# amp-LNA-BGB741L7ESD.net
KiCad netlist of a schematic drawn in EAGLE
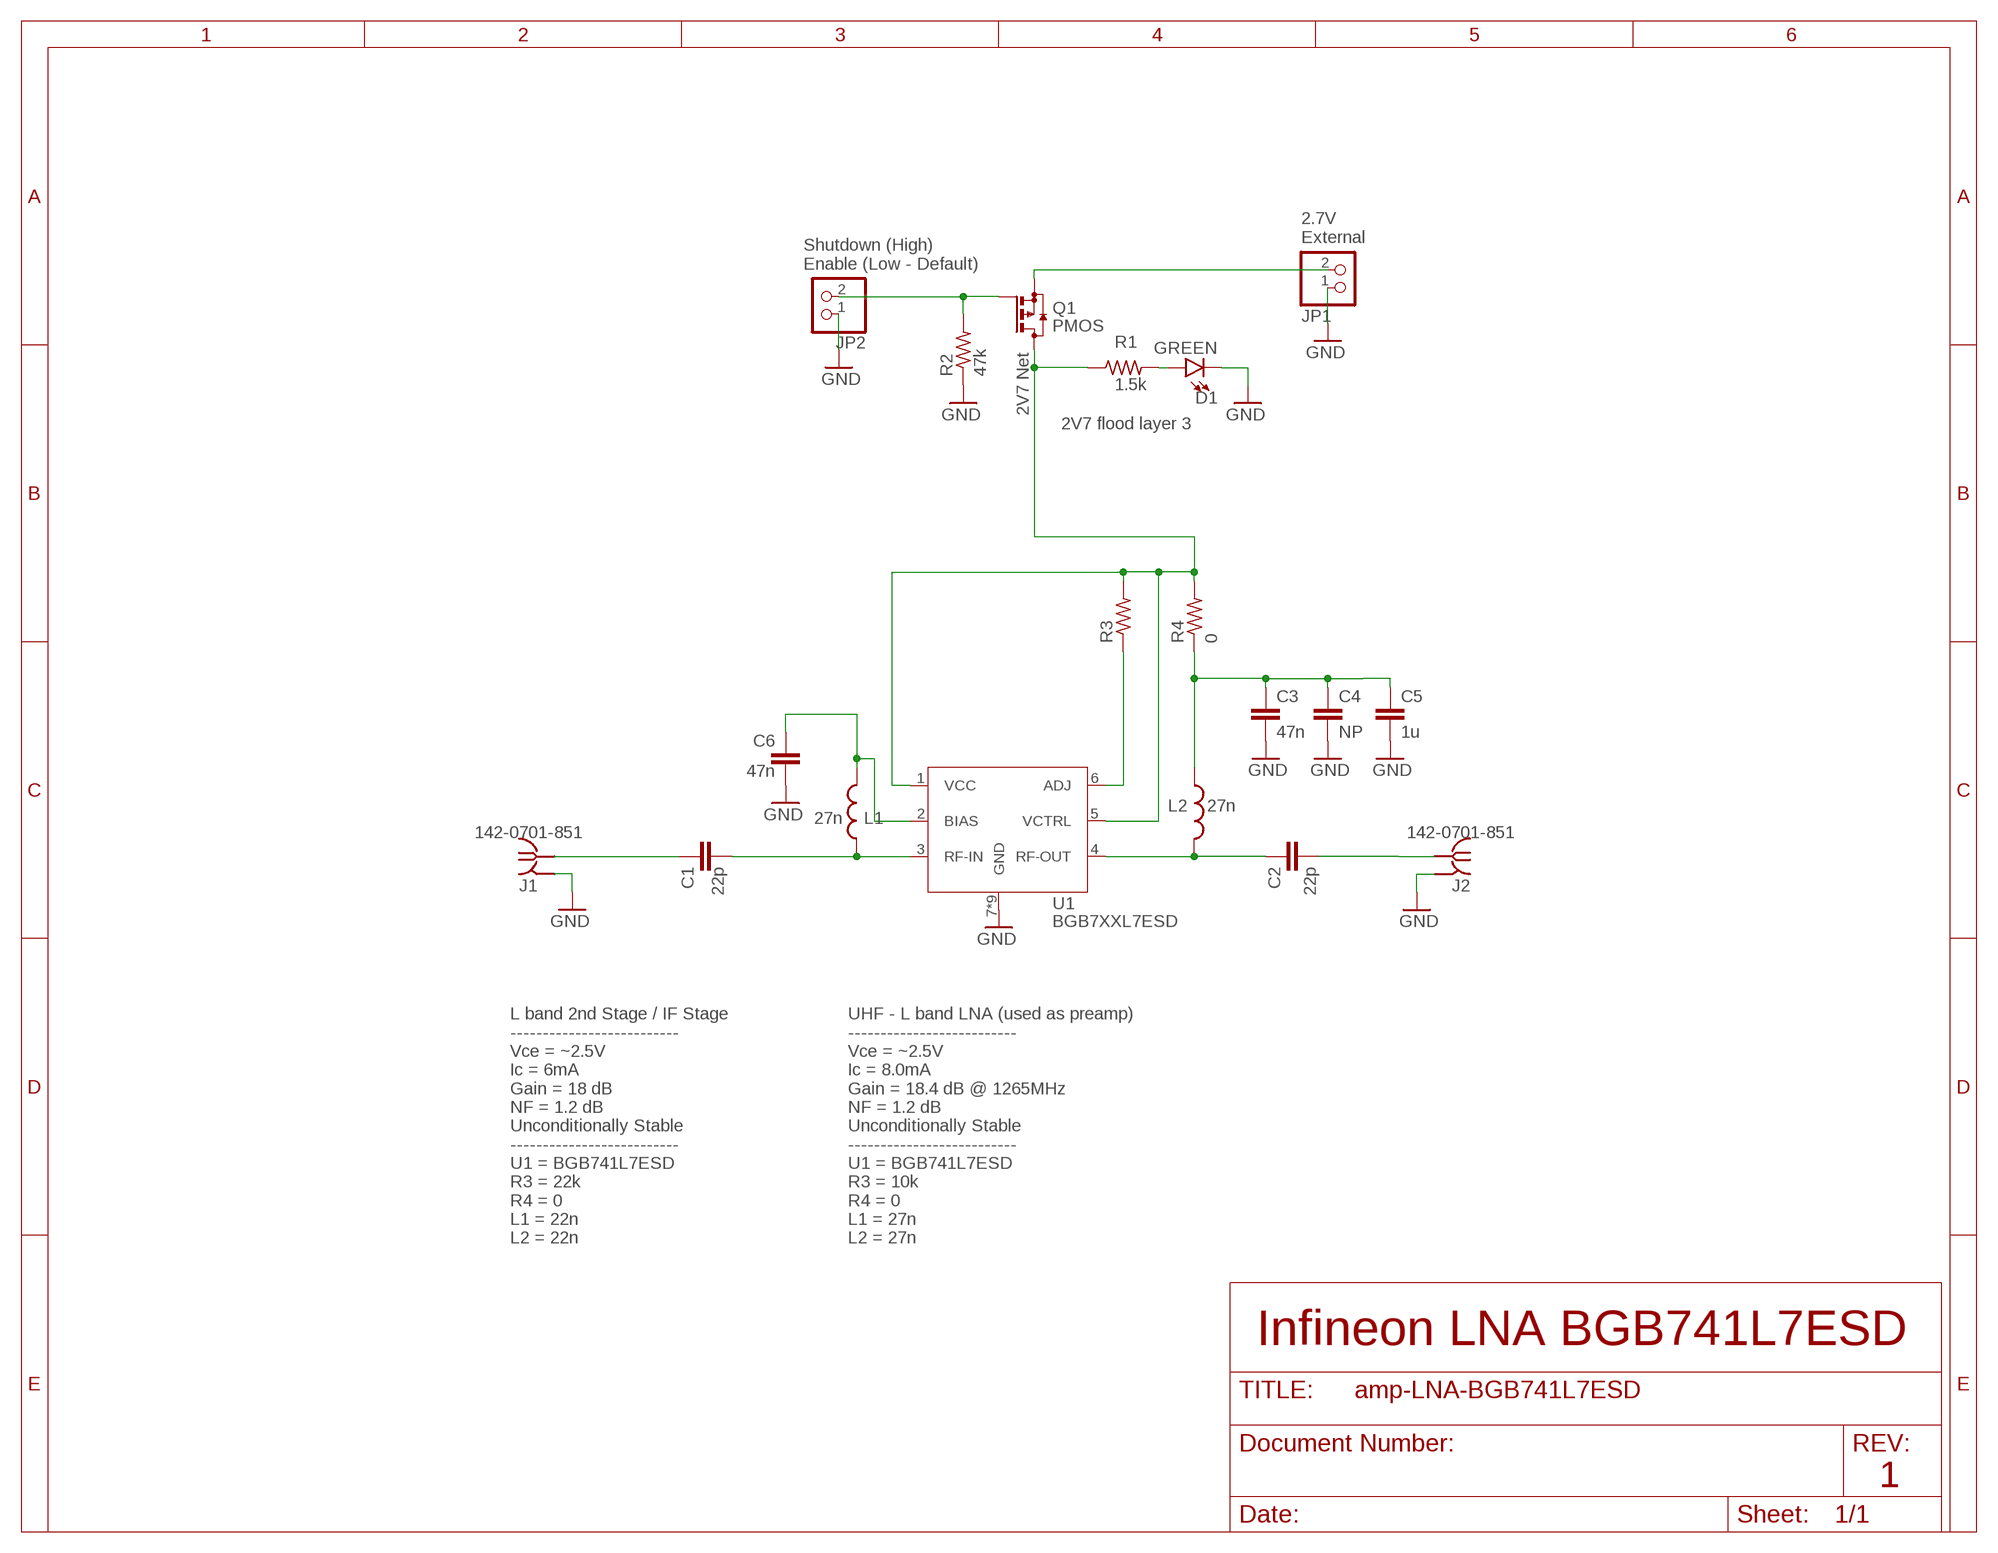
[diagram p0: schematic, sheet 1]

(export (version "E")
  (design (tool "Eeschema 10.0.6"))
  (components
    (comp (ref "C1")
      (value "22p")
      (footprint "eagle-import:.0402-C-NOSILK")
      (libsource (lib "eagle-import") (part "C-EU0402-C-NOSILK"))
    )
    (comp (ref "C2")
      (value "22p")
      (footprint "eagle-import:.0402-C-NOSILK")
      (libsource (lib "eagle-import") (part "C-EU0402-C-NOSILK"))
    )
    (comp (ref "C3")
      (value "47n")
      (footprint "eagle-import:.0603-B-NOSILK")
      (libsource (lib "eagle-import") (part "C-EU0603-B-NOSILK"))
    )
    (comp (ref "C4")
      (value "NP")
      (footprint "eagle-import:.0603-B-NOSILK")
      (libsource (lib "eagle-import") (part "C-EU0603-B-NOSILK"))
    )
    (comp (ref "C5")
      (value "1u")
      (footprint "eagle-import:.0603-B-NOSILK")
      (libsource (lib "eagle-import") (part "C-EU0603-B-NOSILK"))
    )
    (comp (ref "C6")
      (value "47n")
      (footprint "eagle-import:.0603-B-NOSILK")
      (libsource (lib "eagle-import") (part "C-EU0603-B-NOSILK"))
    )
    (comp (ref "D1")
      (value "GREEN")
      (footprint "eagle-import:LED-0603")
      (libsource (lib "eagle-import") (part "LED-GREEN0603"))
    )
    (comp (ref "J1")
      (value "142-0701-851")
      (footprint "eagle-import:142-0701-851")
      (libsource (lib "eagle-import") (part "142-0701-851"))
    )
    (comp (ref "J2")
      (value "142-0701-851")
      (footprint "eagle-import:142-0701-851")
      (libsource (lib "eagle-import") (part "142-0701-851"))
    )
    (comp (ref "JP1")
      (value "PINHD-1X2")
      (footprint "eagle-import:1X02")
      (libsource (lib "eagle-import") (part "PINHD-1X2"))
    )
    (comp (ref "JP2")
      (value "PINHD-1X2")
      (footprint "eagle-import:1X02")
      (libsource (lib "eagle-import") (part "PINHD-1X2"))
    )
    (comp (ref "L1")
      (value "27n")
      (footprint "eagle-import:.0603-C-NOSILK")
      (libsource (lib "eagle-import") (part "L-US0603-C-NOSILK"))
    )
    (comp (ref "L2")
      (value "27n")
      (footprint "eagle-import:.0603-C-NOSILK")
      (libsource (lib "eagle-import") (part "L-US0603-C-NOSILK"))
    )
    (comp (ref "Q1")
      (value "PMOS")
      (footprint "eagle-import:SOT23")
      (libsource (lib "eagle-import") (part "BSS84"))
    )
    (comp (ref "R1")
      (value "1.5k")
      (footprint "eagle-import:.0603-B-NOSILK")
      (libsource (lib "eagle-import") (part "R-US_0603-B-NOSILK"))
    )
    (comp (ref "R2")
      (value "47k")
      (footprint "eagle-import:.0402-B-NOSILK")
      (libsource (lib "eagle-import") (part "R-US_0402-B-NOSILK"))
    )
    (comp (ref "R3")
      (value "27k / NP")
      (footprint "eagle-import:.0603-B-NOSILK")
      (libsource (lib "eagle-import") (part "R-US_0603-B-NOSILK"))
    )
    (comp (ref "R4")
      (value "0")
      (footprint "eagle-import:.0603-B-NOSILK")
      (libsource (lib "eagle-import") (part "R-US_0603-B-NOSILK"))
    )
    (comp (ref "U1")
      (value "BGB7XXL7ESD")
      (footprint "eagle-import:BGB7XXL7ESD")
      (libsource (lib "eagle-import") (part "BGB7XXL7ESD"))
    )
  )
  (nets
    (net (code "1") (name "GND") (class "Default")
      (node (ref "C3") (pin "2") (pinfunction "2_2") (pintype "passive"))
      (node (ref "C4") (pin "2") (pinfunction "2_2") (pintype "passive"))
      (node (ref "C5") (pin "2") (pinfunction "2_2") (pintype "passive"))
      (node (ref "C6") (pin "2") (pinfunction "2_2") (pintype "passive"))
      (node (ref "D1") (pin "C") (pinfunction "C_C") (pintype "passive"))
      (node (ref "J1") (pin "GND1") (pinfunction "GND_GND1") (pintype "bidirectional"))
      (node (ref "J1") (pin "GND2") (pinfunction "GND_GND2") (pintype "bidirectional"))
      (node (ref "J1") (pin "GND3") (pinfunction "GND_GND3") (pintype "bidirectional"))
      (node (ref "J1") (pin "GND4") (pinfunction "GND_GND4") (pintype "bidirectional"))
      (node (ref "J2") (pin "GND1") (pinfunction "GND_GND1") (pintype "bidirectional"))
      (node (ref "J2") (pin "GND2") (pinfunction "GND_GND2") (pintype "bidirectional"))
      (node (ref "J2") (pin "GND3") (pinfunction "GND_GND3") (pintype "bidirectional"))
      (node (ref "J2") (pin "GND4") (pinfunction "GND_GND4") (pintype "bidirectional"))
      (node (ref "JP1") (pin "1") (pinfunction "1_1") (pintype "passive"))
      (node (ref "JP2") (pin "1") (pinfunction "1_1") (pintype "passive"))
      (node (ref "R2") (pin "1") (pinfunction "1_1") (pintype "passive"))
      (node (ref "U1") (pin "10") (pinfunction "GND_10") (pintype "power_in"))
      (node (ref "U1") (pin "11") (pinfunction "GND_11") (pintype "power_in"))
      (node (ref "U1") (pin "12") (pinfunction "GND_12") (pintype "power_in"))
      (node (ref "U1") (pin "13") (pinfunction "GND_13") (pintype "power_in"))
      (node (ref "U1") (pin "14") (pinfunction "GND_14") (pintype "power_in"))
      (node (ref "U1") (pin "15") (pinfunction "GND_15") (pintype "power_in"))
      (node (ref "U1") (pin "7") (pinfunction "GND_7") (pintype "power_in"))
      (node (ref "U1") (pin "8") (pinfunction "GND_8") (pintype "power_in"))
      (node (ref "U1") (pin "9") (pinfunction "GND_9") (pintype "power_in"))
    )
    (net (code "2") (name "Net-(C3-Pad1)") (class "Default")
      (node (ref "C3") (pin "1") (pinfunction "1_1") (pintype "passive"))
      (node (ref "C4") (pin "1") (pinfunction "1_1") (pintype "passive"))
      (node (ref "C5") (pin "1") (pinfunction "1_1") (pintype "passive"))
      (node (ref "L2") (pin "1") (pinfunction "1_1") (pintype "passive"))
      (node (ref "R4") (pin "1") (pinfunction "1_1") (pintype "passive"))
    )
    (net (code "3") (name "Net-(D1-PadA)") (class "Default")
      (node (ref "D1") (pin "A") (pinfunction "A_A") (pintype "passive"))
      (node (ref "R1") (pin "2") (pinfunction "2_2") (pintype "passive"))
    )
    (net (code "4") (name "Net-(J1-RF)") (class "Default")
      (node (ref "C1") (pin "1") (pinfunction "1_1") (pintype "passive"))
      (node (ref "J1") (pin "RF1") (pinfunction "RF_RF1") (pintype "bidirectional"))
    )
    (net (code "5") (name "Net-(J2-RF)") (class "Default")
      (node (ref "C2") (pin "2") (pinfunction "2_2") (pintype "passive"))
      (node (ref "J2") (pin "RF1") (pinfunction "RF_RF1") (pintype "bidirectional"))
    )
    (net (code "6") (name "Net-(Q1-D)") (class "Default")
      (node (ref "Q1") (pin "3") (pinfunction "D_3") (pintype "passive"))
      (node (ref "R1") (pin "1") (pinfunction "1_1") (pintype "passive"))
      (node (ref "R3") (pin "2") (pinfunction "2_2") (pintype "passive"))
      (node (ref "R4") (pin "2") (pinfunction "2_2") (pintype "passive"))
      (node (ref "U1") (pin "1") (pinfunction "VCC_1") (pintype "power_in"))
      (node (ref "U1") (pin "5") (pinfunction "VCTRL_5") (pintype "input"))
    )
    (net (code "7") (name "Net-(Q1-G)") (class "Default")
      (node (ref "JP2") (pin "2") (pinfunction "2_2") (pintype "passive"))
      (node (ref "Q1") (pin "1") (pinfunction "G_1") (pintype "passive"))
      (node (ref "R2") (pin "2") (pinfunction "2_2") (pintype "passive"))
    )
    (net (code "8") (name "Net-(Q1-S)") (class "Default")
      (node (ref "JP1") (pin "2") (pinfunction "2_2") (pintype "passive"))
      (node (ref "Q1") (pin "2") (pinfunction "S_2") (pintype "passive"))
    )
    (net (code "9") (name "Net-(U1-ADJ)") (class "Default")
      (node (ref "R3") (pin "1") (pinfunction "1_1") (pintype "passive"))
      (node (ref "U1") (pin "6") (pinfunction "ADJ_6") (pintype "power_in"))
    )
    (net (code "10") (name "Net-(U1-BIAS)") (class "Default")
      (node (ref "C6") (pin "1") (pinfunction "1_1") (pintype "passive"))
      (node (ref "L1") (pin "2") (pinfunction "2_2") (pintype "passive"))
      (node (ref "U1") (pin "2") (pinfunction "BIAS_2") (pintype "bidirectional"))
    )
    (net (code "11") (name "Net-(U1-RF-IN)") (class "Default")
      (node (ref "C1") (pin "2") (pinfunction "2_2") (pintype "passive"))
      (node (ref "L1") (pin "1") (pinfunction "1_1") (pintype "passive"))
      (node (ref "U1") (pin "3") (pinfunction "RF-IN_3") (pintype "input"))
    )
    (net (code "12") (name "Net-(U1-RF-OUT)") (class "Default")
      (node (ref "C2") (pin "1") (pinfunction "1_1") (pintype "passive"))
      (node (ref "L2") (pin "2") (pinfunction "2_2") (pintype "passive"))
      (node (ref "U1") (pin "4") (pinfunction "RF-OUT_4") (pintype "output"))
    )
  )
)
